# QTR.net
KiCad netlist of a schematic drawn in Altium Designer
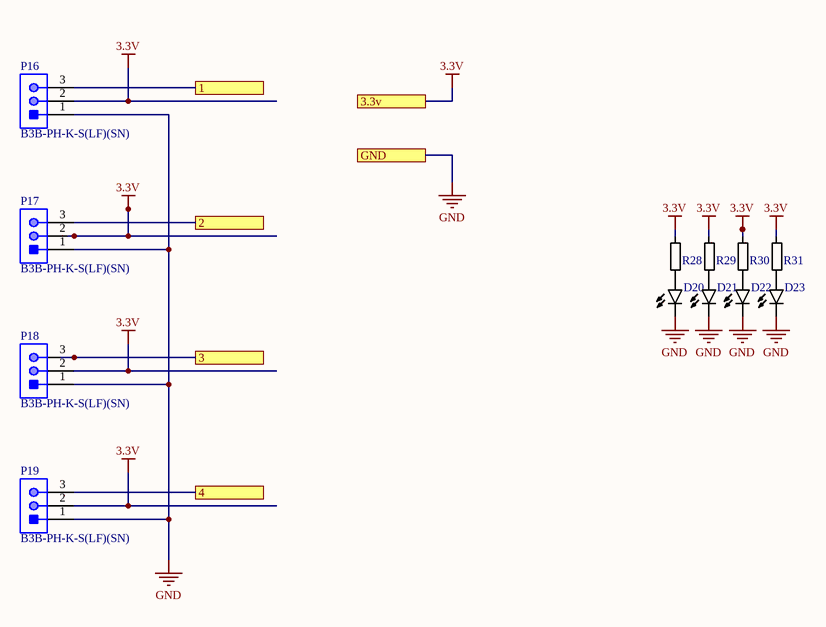
[diagram p0: QTR.SchDoc]

(export (version "E")
  (design (tool "Eeschema 10.0.6"))
  (components
    (comp (ref "D20")
      (value "597-3305-607F")
      (footprint "0805 LED")
      (description "LED Uni-Color Green 4-Pin Chip 0805 T/R")
      (libsource (lib "597-3305-607F") (part "597-3305-607F"))
    )
    (comp (ref "D21")
      (value "597-3305-607F")
      (footprint "0805 LED")
      (description "LED Uni-Color Green 4-Pin Chip 0805 T/R")
      (libsource (lib "597-3305-607F") (part "597-3305-607F"))
    )
    (comp (ref "D22")
      (value "597-3305-607F")
      (footprint "0805 LED")
      (description "LED Uni-Color Green 4-Pin Chip 0805 T/R")
      (libsource (lib "597-3305-607F") (part "597-3305-607F"))
    )
    (comp (ref "D23")
      (value "597-3305-607F")
      (footprint "0805 LED")
      (description "LED Uni-Color Green 4-Pin Chip 0805 T/R")
      (libsource (lib "597-3305-607F") (part "597-3305-607F"))
    )
    (comp (ref "P16")
      (value "B3B-PH-K-S(LF)(SN)")
      (footprint "JST-B3B-PH-K-S-3_V")
      (fields (field (name "MANUFACTURER") "JST"))
      (libsource (lib "Altium Content Vault") (part "CN-1P-M-R3"))
    )
    (comp (ref "P17")
      (value "B3B-PH-K-S(LF)(SN)")
      (footprint "JST-B3B-PH-K-S-3_V")
      (fields (field (name "MANUFACTURER") "JST"))
      (libsource (lib "Altium Content Vault") (part "CN-1P-M-R3"))
    )
    (comp (ref "P18")
      (value "B3B-PH-K-S(LF)(SN)")
      (footprint "JST-B3B-PH-K-S-3_V")
      (fields (field (name "MANUFACTURER") "JST"))
      (libsource (lib "Altium Content Vault") (part "CN-1P-M-R3"))
    )
    (comp (ref "P19")
      (value "B3B-PH-K-S(LF)(SN)")
      (footprint "JST-B3B-PH-K-S-3_V")
      (fields (field (name "MANUFACTURER") "JST"))
      (libsource (lib "Altium Content Vault") (part "CN-1P-M-R3"))
    )
    (comp (ref "R28")
      (value "CR0805-JW-221ELF")
      (footprint "0805 res")
      (description "220 Ohms Â±5% 0.125W, 1/8W Chip Resistor 0805 (2012 Metric) Moisture Resistant Thick Film")
      (fields (field (name "MF") "Bourns"))
      (libsource (lib "CR0805-JW-221ELF") (part "CR0805-JW-221ELF"))
    )
    (comp (ref "R29")
      (value "CR0805-JW-221ELF")
      (footprint "0805 res")
      (description "220 Ohms Â±5% 0.125W, 1/8W Chip Resistor 0805 (2012 Metric) Moisture Resistant Thick Film")
      (fields (field (name "MF") "Bourns"))
      (libsource (lib "CR0805-JW-221ELF") (part "CR0805-JW-221ELF"))
    )
    (comp (ref "R30")
      (value "CR0805-JW-221ELF")
      (footprint "0805 res")
      (description "220 Ohms Â±5% 0.125W, 1/8W Chip Resistor 0805 (2012 Metric) Moisture Resistant Thick Film")
      (fields (field (name "MF") "Bourns"))
      (libsource (lib "CR0805-JW-221ELF") (part "CR0805-JW-221ELF"))
    )
    (comp (ref "R31")
      (value "CR0805-JW-221ELF")
      (footprint "0805 res")
      (description "220 Ohms Â±5% 0.125W, 1/8W Chip Resistor 0805 (2012 Metric) Moisture Resistant Thick Film")
      (fields (field (name "MF") "Bourns"))
      (libsource (lib "CR0805-JW-221ELF") (part "CR0805-JW-221ELF"))
    )
  )
  (nets
    (net (code "1") (name "/1") (class "Default")
      (node (ref "P16") (pin "3") (pinfunction "3_3") (pintype "passive"))
    )
    (net (code "2") (name "/2") (class "Default")
      (node (ref "P17") (pin "3") (pinfunction "3_3") (pintype "passive"))
    )
    (net (code "3") (name "/3") (class "Default")
      (node (ref "P18") (pin "3") (pinfunction "3_3") (pintype "passive"))
    )
    (net (code "4") (name "/4") (class "Default")
      (node (ref "P19") (pin "3") (pinfunction "3_3") (pintype "passive"))
    )
    (net (code "5") (name "3.3V") (class "Default")
      (node (ref "P16") (pin "2") (pinfunction "2_2") (pintype "passive"))
      (node (ref "P17") (pin "2") (pinfunction "2_2") (pintype "passive"))
      (node (ref "P18") (pin "2") (pinfunction "2_2") (pintype "passive"))
      (node (ref "P19") (pin "2") (pinfunction "2_2") (pintype "passive"))
      (node (ref "R28") (pin "1") (pinfunction "1_1") (pintype "passive"))
      (node (ref "R29") (pin "1") (pinfunction "1_1") (pintype "passive"))
      (node (ref "R30") (pin "1") (pinfunction "1_1") (pintype "passive"))
      (node (ref "R31") (pin "1") (pinfunction "1_1") (pintype "passive"))
    )
    (net (code "6") (name "GND") (class "Default")
      (node (ref "D20") (pin "C") (pinfunction "C_C") (pintype "passive"))
      (node (ref "D21") (pin "C") (pinfunction "C_C") (pintype "passive"))
      (node (ref "D22") (pin "C") (pinfunction "C_C") (pintype "passive"))
      (node (ref "D23") (pin "C") (pinfunction "C_C") (pintype "passive"))
      (node (ref "P16") (pin "1") (pinfunction "1_1") (pintype "passive"))
      (node (ref "P17") (pin "1") (pinfunction "1_1") (pintype "passive"))
      (node (ref "P18") (pin "1") (pinfunction "1_1") (pintype "passive"))
      (node (ref "P19") (pin "1") (pinfunction "1_1") (pintype "passive"))
    )
    (net (code "7") (name "Net-(D20-PadA)") (class "Default")
      (node (ref "D20") (pin "A") (pinfunction "A_A") (pintype "passive"))
      (node (ref "R28") (pin "2") (pinfunction "2_2") (pintype "passive"))
    )
    (net (code "8") (name "Net-(D21-PadA)") (class "Default")
      (node (ref "D21") (pin "A") (pinfunction "A_A") (pintype "passive"))
      (node (ref "R29") (pin "2") (pinfunction "2_2") (pintype "passive"))
    )
    (net (code "9") (name "Net-(D22-PadA)") (class "Default")
      (node (ref "D22") (pin "A") (pinfunction "A_A") (pintype "passive"))
      (node (ref "R30") (pin "2") (pinfunction "2_2") (pintype "passive"))
    )
    (net (code "10") (name "Net-(D23-PadA)") (class "Default")
      (node (ref "D23") (pin "A") (pinfunction "A_A") (pintype "passive"))
      (node (ref "R31") (pin "2") (pinfunction "2_2") (pintype "passive"))
    )
  )
)
